# TSAL-TS.net
KiCad netlist of a schematic drawn in EAGLE
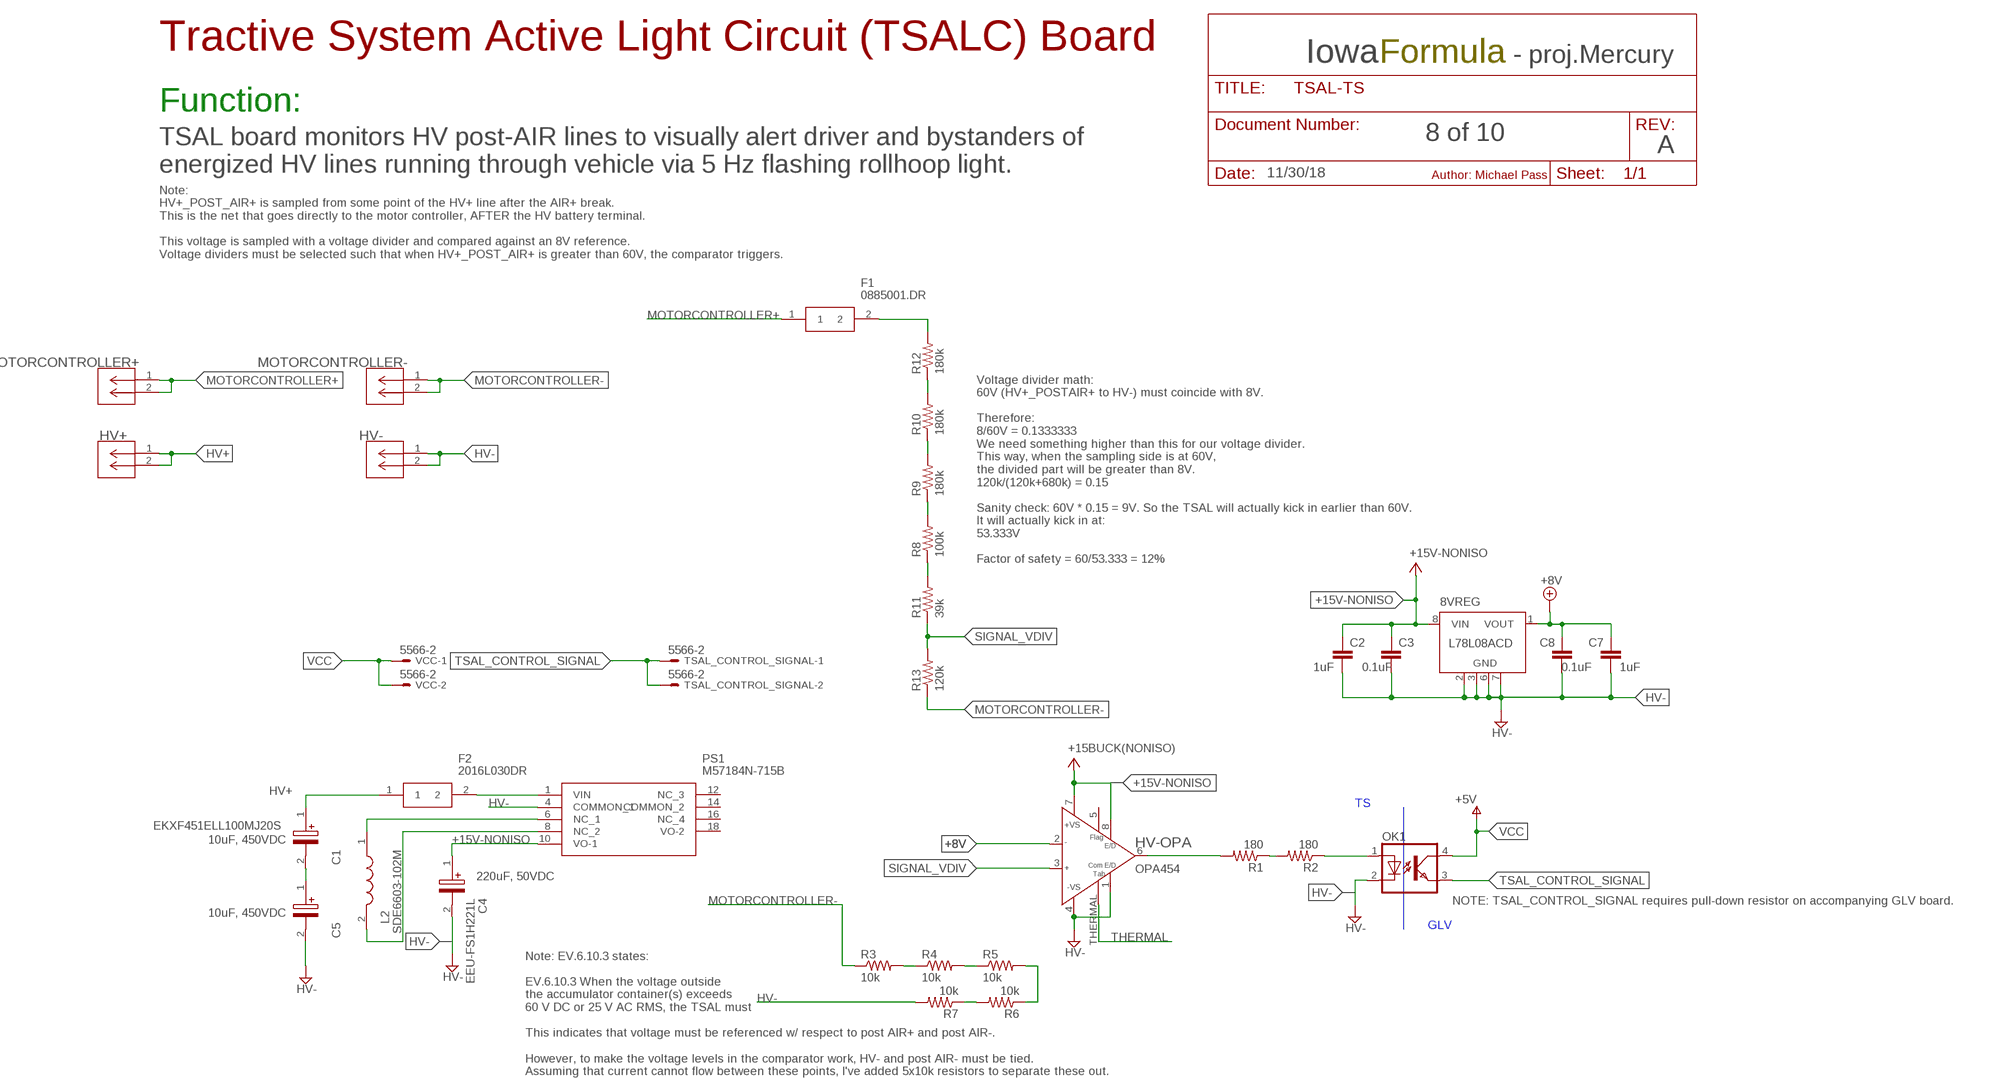
[diagram p0: schematic, sheet 1]

(export (version "E")
  (design (tool "Eeschema 10.0.6"))
  (components
    (comp (ref "8VREG")
      (value "L78L08ACD")
      (footprint "eagle-import:SO08")
      (libsource (lib "eagle-import") (part "78LSMD08"))
    )
    (comp (ref "C1")
      (value "EKXF451ELL100MJ20S")
      (footprint "eagle-import:CAPPRD500W60D1025H2150")
      (fields (field (name "MOUSER_PART_NUMBER") "661-EKXF451ELL100MJ2"))
      (libsource (lib "eagle-import") (part "EKXF451ELL100MJ20S"))
    )
    (comp (ref "C2")
      (value "1uF")
      (footprint "eagle-import:C0805")
      (libsource (lib "eagle-import") (part "C-EUC0805"))
    )
    (comp (ref "C3")
      (value "0.1uF")
      (footprint "eagle-import:C0805")
      (libsource (lib "eagle-import") (part "C-EUC0805"))
    )
    (comp (ref "C4")
      (value "EEU-FS1H221L")
      (footprint "eagle-import:CAPPRD350W65D800H2200")
      (fields (field (name "MOUSER_PART_NUMBER") "667-EEU-FS1H221L"))
      (libsource (lib "eagle-import") (part "EEU-FS1H221L"))
    )
    (comp (ref "C5")
      (value "EKXF451ELL100MJ20S")
      (footprint "eagle-import:CAPPRD500W60D1025H2150")
      (fields (field (name "MOUSER_PART_NUMBER") "661-EKXF451ELL100MJ2"))
      (libsource (lib "eagle-import") (part "EKXF451ELL100MJ20S"))
    )
    (comp (ref "C7")
      (value "1uF")
      (footprint "eagle-import:C0805")
      (libsource (lib "eagle-import") (part "C-EUC0805"))
    )
    (comp (ref "C8")
      (value "0.1uF")
      (footprint "eagle-import:C0805")
      (libsource (lib "eagle-import") (part "C-EUC0805"))
    )
    (comp (ref "F1")
      (value "0885001.DR")
      (footprint "eagle-import:FUSC10948X488N")
      (fields (field (name "MOUSER_PART_NUMBER") "576-0885001.DR"))
      (libsource (lib "eagle-import") (part "0885001.DR"))
    )
    (comp (ref "F2")
      (value "2016L030DR")
      (footprint "eagle-import:FUSC5141X125N")
      (fields (field (name "MOUSER_PART_NUMBER") "576-2016L030DR"))
      (libsource (lib "eagle-import") (part "2016L030DR"))
    )
    (comp (ref "HV+")
      (value "2P_1-770166-0")
      (footprint "eagle-import:CON2_1X2_P163_VMNL-1MTG")
      (fields (field (name "MANUFACTURER_PART_NUMBER") "17701660"))
      (libsource (lib "eagle-import") (part "2P_1-770166-0"))
    )
    (comp (ref "HV-")
      (value "2P_1-770166-0")
      (footprint "eagle-import:CON2_1X2_P163_VMNL-1MTG")
      (fields (field (name "MANUFACTURER_PART_NUMBER") "17701660"))
      (libsource (lib "eagle-import") (part "2P_1-770166-0"))
    )
    (comp (ref "HV-OPA")
      (value "OPA454")
      (footprint "eagle-import:SO08GP")
      (fields (field (name "MF") "Texas Instruments"))
      (libsource (lib "eagle-import") (part "OPA454"))
    )
    (comp (ref "L2")
      (value "SDE6603-102M")
      (footprint "eagle-import:SDE6603")
      (fields (field (name "MOUSER_PART_NUMBER") "652-SDE6603-102M"))
      (libsource (lib "eagle-import") (part "SDE6603-102M"))
    )
    (comp (ref "MOTORCONTROLLER+")
      (value "2P_1-770166-0")
      (footprint "eagle-import:CON2_1X2_P163_VMNL-1MTG")
      (fields (field (name "MANUFACTURER_PART_NUMBER") "17701660"))
      (libsource (lib "eagle-import") (part "2P_1-770166-0"))
    )
    (comp (ref "MOTORCONTROLLER-")
      (value "2P_1-770166-0")
      (footprint "eagle-import:CON2_1X2_P163_VMNL-1MTG")
      (fields (field (name "MANUFACTURER_PART_NUMBER") "17701660"))
      (libsource (lib "eagle-import") (part "2P_1-770166-0"))
    )
    (comp (ref "OK1")
      (value "PC817-S")
      (footprint "eagle-import:SOP04(2.54)")
      (libsource (lib "eagle-import") (part "PC817-S"))
    )
    (comp (ref "PS1")
      (value "M57184N-715B")
      (footprint "eagle-import:M57184N715B")
      (libsource (lib "eagle-import") (part "M57184N-715B"))
    )
    (comp (ref "R1")
      (value "180")
      (footprint "eagle-import:R0805")
      (libsource (lib "eagle-import") (part "R-US_R0805"))
    )
    (comp (ref "R2")
      (value "180")
      (footprint "eagle-import:R0805")
      (libsource (lib "eagle-import") (part "R-US_R0805"))
    )
    (comp (ref "R3")
      (value "10k")
      (footprint "eagle-import:R0805")
      (libsource (lib "eagle-import") (part "R-US_R0805"))
    )
    (comp (ref "R4")
      (value "10k")
      (footprint "eagle-import:R0805")
      (libsource (lib "eagle-import") (part "R-US_R0805"))
    )
    (comp (ref "R5")
      (value "10k")
      (footprint "eagle-import:R0805")
      (libsource (lib "eagle-import") (part "R-US_R0805"))
    )
    (comp (ref "R6")
      (value "10k")
      (footprint "eagle-import:R0805")
      (libsource (lib "eagle-import") (part "R-US_R0805"))
    )
    (comp (ref "R7")
      (value "10k")
      (footprint "eagle-import:R0805")
      (libsource (lib "eagle-import") (part "R-US_R0805"))
    )
    (comp (ref "R8")
      (value "100k")
      (footprint "eagle-import:R0805")
      (libsource (lib "eagle-import") (part "R-US_R0805"))
    )
    (comp (ref "R9")
      (value "180k")
      (footprint "eagle-import:R0805")
      (libsource (lib "eagle-import") (part "R-US_R0805"))
    )
    (comp (ref "R10")
      (value "180k")
      (footprint "eagle-import:R0805")
      (libsource (lib "eagle-import") (part "R-US_R0805"))
    )
    (comp (ref "R11")
      (value "39k")
      (footprint "eagle-import:R0805")
      (libsource (lib "eagle-import") (part "R-US_R0805"))
    )
    (comp (ref "R12")
      (value "180k")
      (footprint "eagle-import:R0805")
      (libsource (lib "eagle-import") (part "R-US_R0805"))
    )
    (comp (ref "R13")
      (value "120k")
      (footprint "eagle-import:R0805")
      (libsource (lib "eagle-import") (part "R-US_R0805"))
    )
    (comp (ref "TSAL_CONTROL_SIGNAL")
      (value "5566-2")
      (footprint "eagle-import:5566-2")
      (fields (field (name "MF") "MOLEX"))
      (libsource (lib "eagle-import") (part "5566-2"))
    )
    (comp (ref "VCC")
      (value "5566-2")
      (footprint "eagle-import:5566-2")
      (fields (field (name "MF") "MOLEX"))
      (libsource (lib "eagle-import") (part "5566-2"))
    )
  )
  (nets
    (net (code "1") (name "+8V") (class "Default")
      (node (ref "8VREG") (pin "1") (pinfunction "VOUT_1") (pintype "output"))
      (node (ref "C7") (pin "1") (pinfunction "1_1") (pintype "passive"))
      (node (ref "C8") (pin "1") (pinfunction "1_1") (pintype "passive"))
      (node (ref "HV-OPA") (pin "2") (pinfunction "IN-_2") (pintype "input"))
    )
    (net (code "2") (name "+15V-NONISO") (class "Default")
      (node (ref "8VREG") (pin "8") (pinfunction "VIN_8") (pintype "passive"))
      (node (ref "C2") (pin "1") (pinfunction "1_1") (pintype "passive"))
      (node (ref "C3") (pin "1") (pinfunction "1_1") (pintype "passive"))
      (node (ref "C4") (pin "1") (pinfunction "+_1") (pintype "bidirectional"))
      (node (ref "HV-OPA") (pin "7") (pinfunction "+VS_7") (pintype "passive"))
      (node (ref "HV-OPA") (pin "8") (pinfunction "E/D_8") (pintype "passive"))
      (node (ref "PS1") (pin "10") (pinfunction "VO-1_10") (pintype "bidirectional"))
    )
    (net (code "3") (name "/THERMAL") (class "Default")
      (node (ref "HV-OPA") (pin "THERMAL") (pinfunction "E/DCOM1_THERMAL") (pintype "passive"))
    )
    (net (code "4") (name "HV+") (class "Default")
      (node (ref "C1") (pin "1") (pinfunction "+_1") (pintype "bidirectional"))
      (node (ref "F2") (pin "1") (pinfunction "1_1") (pintype "bidirectional"))
      (node (ref "HV+") (pin "1") (pinfunction "1_1") (pintype "passive"))
      (node (ref "HV+") (pin "2") (pinfunction "2_2") (pintype "passive"))
    )
    (net (code "5") (name "HV-") (class "Default")
      (node (ref "8VREG") (pin "2") (pinfunction "GND_2") (pintype "power_in"))
      (node (ref "8VREG") (pin "3") (pinfunction "GND_3") (pintype "power_in"))
      (node (ref "8VREG") (pin "6") (pinfunction "GND_6") (pintype "power_in"))
      (node (ref "8VREG") (pin "7") (pinfunction "GND_7") (pintype "power_in"))
      (node (ref "C2") (pin "2") (pinfunction "2_2") (pintype "passive"))
      (node (ref "C3") (pin "2") (pinfunction "2_2") (pintype "passive"))
      (node (ref "C4") (pin "2") (pinfunction "-_2") (pintype "bidirectional"))
      (node (ref "C5") (pin "2") (pinfunction "-_2") (pintype "bidirectional"))
      (node (ref "C7") (pin "2") (pinfunction "2_2") (pintype "passive"))
      (node (ref "C8") (pin "2") (pinfunction "2_2") (pintype "passive"))
      (node (ref "HV-") (pin "1") (pinfunction "1_1") (pintype "passive"))
      (node (ref "HV-") (pin "2") (pinfunction "2_2") (pintype "passive"))
      (node (ref "HV-OPA") (pin "1") (pinfunction "E/DCOM_1") (pintype "passive"))
      (node (ref "HV-OPA") (pin "4") (pinfunction "-VS_4") (pintype "passive"))
      (node (ref "OK1") (pin "2") (pinfunction "C_2") (pintype "passive"))
      (node (ref "PS1") (pin "4") (pinfunction "COMMON_1_4") (pintype "bidirectional"))
      (node (ref "R7") (pin "2") (pinfunction "2_2") (pintype "passive"))
    )
    (net (code "6") (name "MOTORCONTROLLER+") (class "Default")
      (node (ref "F1") (pin "1") (pinfunction "1_1") (pintype "bidirectional"))
      (node (ref "MOTORCONTROLLER+") (pin "1") (pinfunction "1_1") (pintype "passive"))
      (node (ref "MOTORCONTROLLER+") (pin "2") (pinfunction "2_2") (pintype "passive"))
    )
    (net (code "7") (name "MOTORCONTROLLER-") (class "Default")
      (node (ref "MOTORCONTROLLER-") (pin "1") (pinfunction "1_1") (pintype "passive"))
      (node (ref "MOTORCONTROLLER-") (pin "2") (pinfunction "2_2") (pintype "passive"))
      (node (ref "R13") (pin "1") (pinfunction "1_1") (pintype "passive"))
      (node (ref "R3") (pin "1") (pinfunction "1_1") (pintype "passive"))
    )
    (net (code "8") (name "Net-(C1--)") (class "Default")
      (node (ref "C1") (pin "2") (pinfunction "-_2") (pintype "bidirectional"))
      (node (ref "C5") (pin "1") (pinfunction "+_1") (pintype "bidirectional"))
    )
    (net (code "9") (name "Net-(F1-Pad2)") (class "Default")
      (node (ref "F1") (pin "2") (pinfunction "2_2") (pintype "bidirectional"))
      (node (ref "R12") (pin "2") (pinfunction "2_2") (pintype "passive"))
    )
    (net (code "10") (name "Net-(HV-OPA-OUT)") (class "Default")
      (node (ref "HV-OPA") (pin "6") (pinfunction "OUT_6") (pintype "output"))
      (node (ref "R1") (pin "2") (pinfunction "2_2") (pintype "passive"))
    )
    (net (code "11") (name "Net-(OK1-A)") (class "Default")
      (node (ref "OK1") (pin "1") (pinfunction "A_1") (pintype "passive"))
      (node (ref "R2") (pin "1") (pinfunction "1_1") (pintype "passive"))
    )
    (net (code "12") (name "Net-(PS1-NC_1)") (class "Default")
      (node (ref "L2") (pin "1") (pinfunction "1_1") (pintype "bidirectional"))
      (node (ref "PS1") (pin "6") (pinfunction "NC_1_6") (pintype "bidirectional"))
    )
    (net (code "13") (name "Net-(PS1-NC_2)") (class "Default")
      (node (ref "L2") (pin "2") (pinfunction "2_2") (pintype "bidirectional"))
      (node (ref "PS1") (pin "8") (pinfunction "NC_2_8") (pintype "bidirectional"))
    )
    (net (code "14") (name "Net-(PS1-VIN)") (class "Default")
      (node (ref "F2") (pin "2") (pinfunction "2_2") (pintype "bidirectional"))
      (node (ref "PS1") (pin "1") (pinfunction "VIN_1") (pintype "bidirectional"))
    )
    (net (code "15") (name "Net-(R1-Pad1)") (class "Default")
      (node (ref "R1") (pin "1") (pinfunction "1_1") (pintype "passive"))
      (node (ref "R2") (pin "2") (pinfunction "2_2") (pintype "passive"))
    )
    (net (code "16") (name "Net-(R3-Pad2)") (class "Default")
      (node (ref "R3") (pin "2") (pinfunction "2_2") (pintype "passive"))
      (node (ref "R4") (pin "1") (pinfunction "1_1") (pintype "passive"))
    )
    (net (code "17") (name "Net-(R4-Pad2)") (class "Default")
      (node (ref "R4") (pin "2") (pinfunction "2_2") (pintype "passive"))
      (node (ref "R5") (pin "1") (pinfunction "1_1") (pintype "passive"))
    )
    (net (code "18") (name "Net-(R5-Pad2)") (class "Default")
      (node (ref "R5") (pin "2") (pinfunction "2_2") (pintype "passive"))
      (node (ref "R6") (pin "1") (pinfunction "1_1") (pintype "passive"))
    )
    (net (code "19") (name "Net-(R6-Pad2)") (class "Default")
      (node (ref "R6") (pin "2") (pinfunction "2_2") (pintype "passive"))
      (node (ref "R7") (pin "1") (pinfunction "1_1") (pintype "passive"))
    )
    (net (code "20") (name "Net-(R8-Pad2)") (class "Default")
      (node (ref "R8") (pin "2") (pinfunction "2_2") (pintype "passive"))
      (node (ref "R9") (pin "1") (pinfunction "1_1") (pintype "passive"))
    )
    (net (code "21") (name "Net-(R10-Pad1)") (class "Default")
      (node (ref "R10") (pin "1") (pinfunction "1_1") (pintype "passive"))
      (node (ref "R9") (pin "2") (pinfunction "2_2") (pintype "passive"))
    )
    (net (code "22") (name "Net-(R10-Pad2)") (class "Default")
      (node (ref "R10") (pin "2") (pinfunction "2_2") (pintype "passive"))
      (node (ref "R12") (pin "1") (pinfunction "1_1") (pintype "passive"))
    )
    (net (code "23") (name "Net-(R11-Pad2)") (class "Default")
      (node (ref "R11") (pin "2") (pinfunction "2_2") (pintype "passive"))
      (node (ref "R8") (pin "1") (pinfunction "1_1") (pintype "passive"))
    )
    (net (code "24") (name "SIGNAL_VDIV") (class "Default")
      (node (ref "HV-OPA") (pin "3") (pinfunction "IN+_3") (pintype "input"))
      (node (ref "R11") (pin "1") (pinfunction "1_1") (pintype "passive"))
      (node (ref "R13") (pin "2") (pinfunction "2_2") (pintype "passive"))
    )
    (net (code "25") (name "TSAL_CONTROL_SIGNAL") (class "Default")
      (node (ref "OK1") (pin "3") (pinfunction "EMIT_3") (pintype "passive"))
      (node (ref "TSAL_CONTROL_SIGNAL") (pin "1") (pinfunction "S_1") (pintype "passive"))
      (node (ref "TSAL_CONTROL_SIGNAL") (pin "2") (pinfunction "S_2") (pintype "passive"))
    )
    (net (code "26") (name "VCC") (class "Default")
      (node (ref "OK1") (pin "4") (pinfunction "COL_4") (pintype "passive"))
      (node (ref "VCC") (pin "1") (pinfunction "S_1") (pintype "passive"))
      (node (ref "VCC") (pin "2") (pinfunction "S_2") (pintype "passive"))
    )
    (net (code "27") (name "unconnected-(HV-OPA-STATUS-Pad5)") (class "Default")
      (node (ref "HV-OPA") (pin "5") (pinfunction "STATUS_5") (pintype "passive"))
    )
    (net (code "28") (name "unconnected-(PS1-COMMON_2-Pad14)") (class "Default")
      (node (ref "PS1") (pin "14") (pinfunction "COMMON_2_14") (pintype "bidirectional"))
    )
    (net (code "29") (name "unconnected-(PS1-NC_3-Pad12)") (class "Default")
      (node (ref "PS1") (pin "12") (pinfunction "NC_3_12") (pintype "bidirectional"))
    )
    (net (code "30") (name "unconnected-(PS1-NC_4-Pad16)") (class "Default")
      (node (ref "PS1") (pin "16") (pinfunction "NC_4_16") (pintype "bidirectional"))
    )
    (net (code "31") (name "unconnected-(PS1-VO-2-Pad18)") (class "Default")
      (node (ref "PS1") (pin "18") (pinfunction "VO-2_18") (pintype "bidirectional"))
    )
  )
)
